# Adafruit_LIS3MDL_LSM6DSOX_FeatherWing.net
KiCad netlist of a schematic drawn in EAGLE
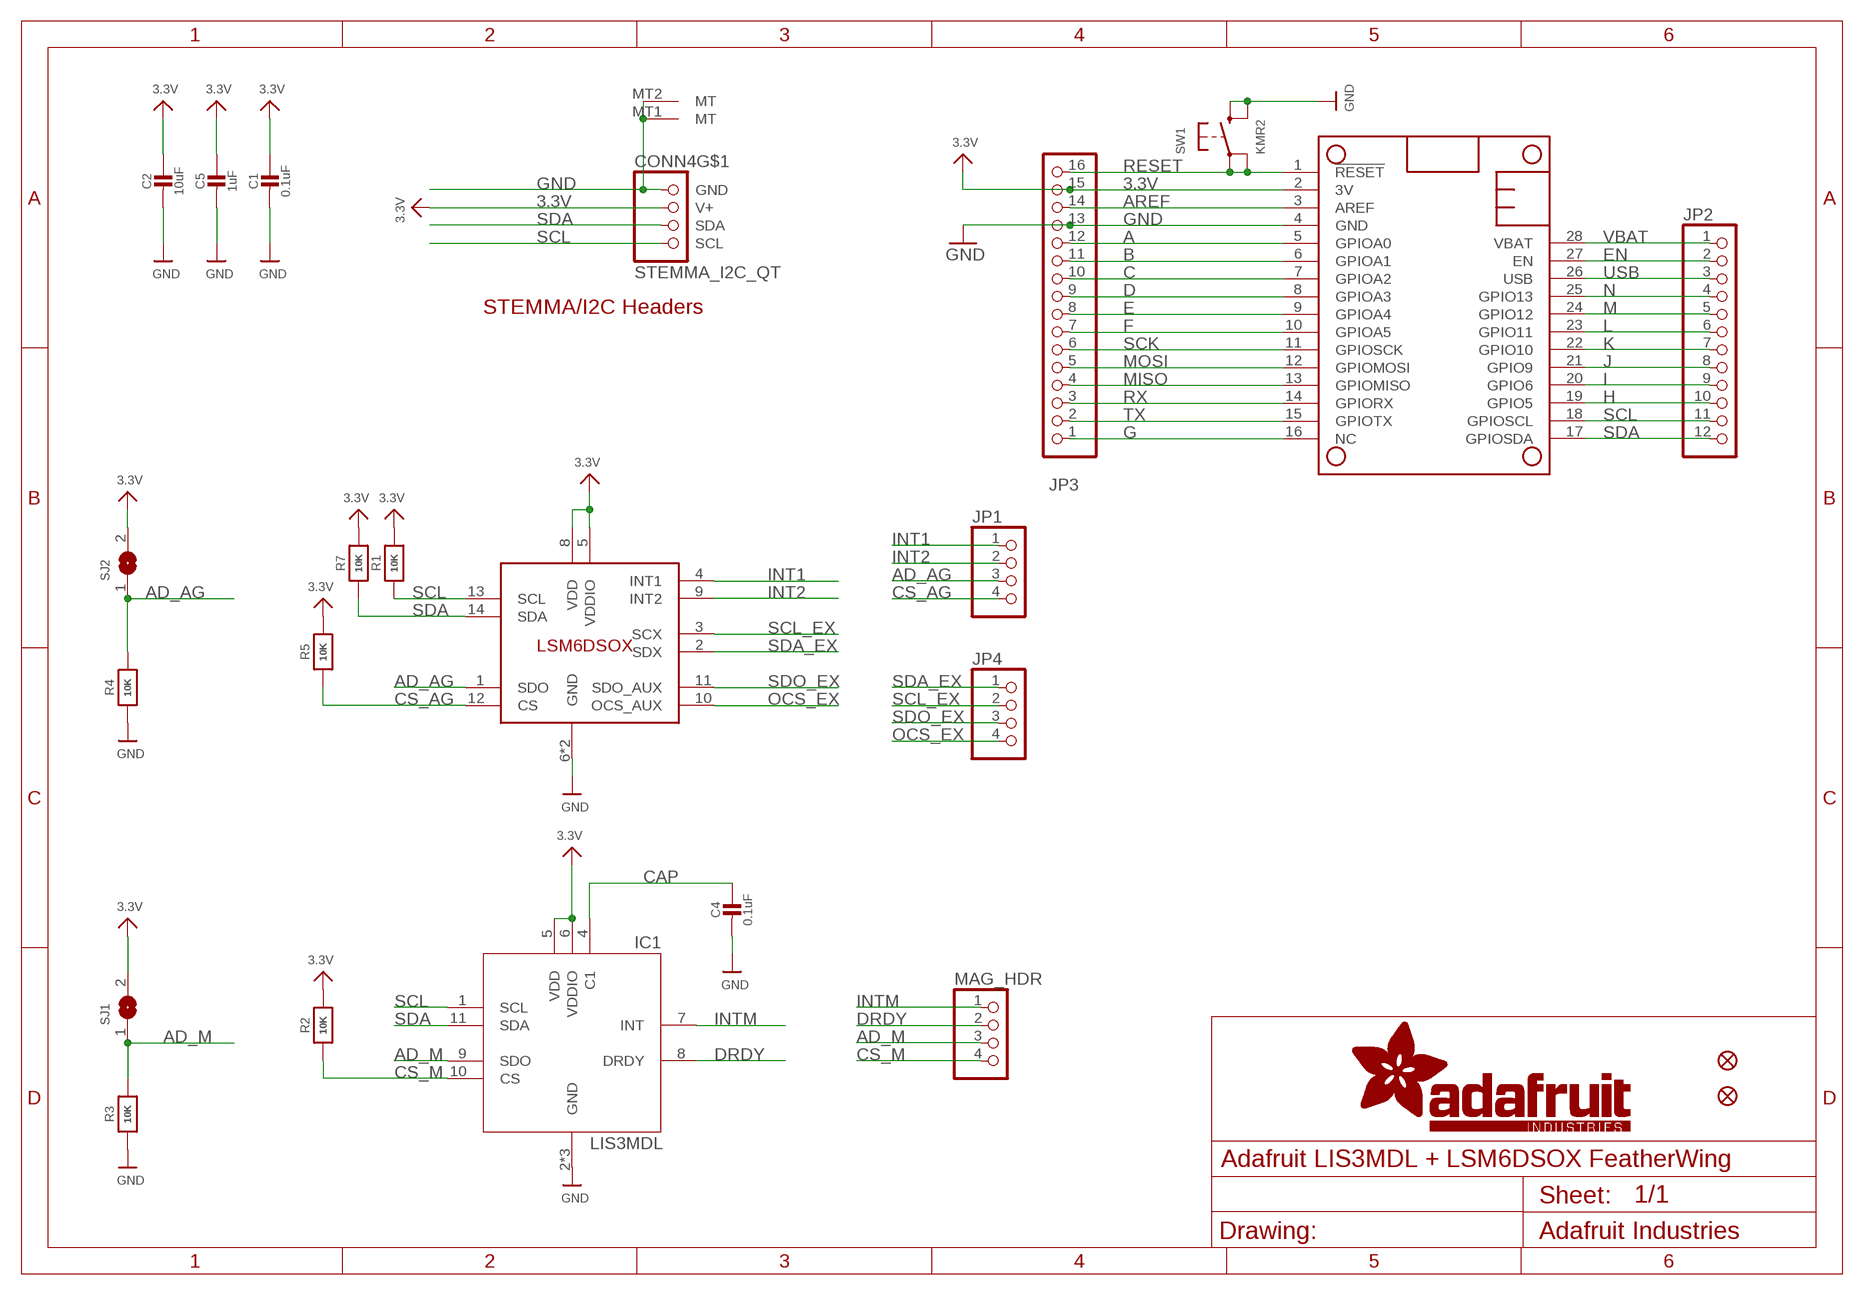
[diagram p0: schematic, sheet 1]

(export (version "E")
  (design (tool "Eeschema 10.0.6"))
  (components
    (comp (ref "C1")
      (value "0.1uF")
      (footprint "eagle-import:0603-NO")
      (libsource (lib "eagle-import") (part "CAP_CERAMIC0603_NO"))
    )
    (comp (ref "C2")
      (value "10uF")
      (footprint "eagle-import:0805-NO")
      (libsource (lib "eagle-import") (part "CAP_CERAMIC0805-NOOUTLINE"))
    )
    (comp (ref "C4")
      (value "0.1uF")
      (footprint "eagle-import:0603-NO")
      (libsource (lib "eagle-import") (part "CAP_CERAMIC0603_NO"))
    )
    (comp (ref "C5")
      (value "1uF")
      (footprint "eagle-import:0603-NO")
      (libsource (lib "eagle-import") (part "CAP_CERAMIC0603_NO"))
    )
    (comp (ref "CONN4")
      (value "STEMMA_I2C_QT")
      (footprint "eagle-import:JST_SH4")
      (libsource (lib "eagle-import") (part "STEMMA_I2C_QT"))
    )
    (comp (ref "FID1")
      (value "FIDUCIAL_1MM")
      (footprint "eagle-import:FIDUCIAL_1MM")
      (libsource (lib "eagle-import") (part "FIDUCIAL_1MM"))
    )
    (comp (ref "FID2")
      (value "FIDUCIAL_1MM")
      (footprint "eagle-import:FIDUCIAL_1MM")
      (libsource (lib "eagle-import") (part "FIDUCIAL_1MM"))
    )
    (comp (ref "IC1")
      (value "LIS3MDL")
      (footprint "eagle-import:LGA12_2X2MM")
      (libsource (lib "eagle-import") (part "LIS3MDL"))
    )
    (comp (ref "JP1")
      (value "HEADER-1X4ROUND")
      (footprint "eagle-import:1X04_ROUND")
      (libsource (lib "eagle-import") (part "HEADER-1X4ROUND"))
    )
    (comp (ref "JP2")
      (value "HEADER-1X12")
      (footprint "eagle-import:1X12_ROUND")
      (libsource (lib "eagle-import") (part "HEADER-1X12"))
    )
    (comp (ref "JP3")
      (value "HEADER-1X16ROUND")
      (footprint "eagle-import:1X16_ROUND")
      (libsource (lib "eagle-import") (part "HEADER-1X16ROUND"))
    )
    (comp (ref "JP4")
      (value "HEADER-1X4ROUND")
      (footprint "eagle-import:1X04_ROUND")
      (libsource (lib "eagle-import") (part "HEADER-1X4ROUND"))
    )
    (comp (ref "MAG_HDR")
      (value "HEADER-1X4ROUND")
      (footprint "eagle-import:1X04_ROUND")
      (libsource (lib "eagle-import") (part "HEADER-1X4ROUND"))
    )
    (comp (ref "MS1")
      (value "FEATHERWING")
      (footprint "eagle-import:FEATHERWING")
      (libsource (lib "eagle-import") (part "FEATHERWING"))
    )
    (comp (ref "R1")
      (value "10K")
      (footprint "eagle-import:0603-NO")
      (libsource (lib "eagle-import") (part "RESISTOR_0603_NOOUT"))
    )
    (comp (ref "R2")
      (value "10K")
      (footprint "eagle-import:0603-NO")
      (libsource (lib "eagle-import") (part "RESISTOR_0603_NOOUT"))
    )
    (comp (ref "R3")
      (value "10K")
      (footprint "eagle-import:0603-NO")
      (libsource (lib "eagle-import") (part "RESISTOR_0603_NOOUT"))
    )
    (comp (ref "R4")
      (value "10K")
      (footprint "eagle-import:0603-NO")
      (libsource (lib "eagle-import") (part "RESISTOR_0603_NOOUT"))
    )
    (comp (ref "R5")
      (value "10K")
      (footprint "eagle-import:0603-NO")
      (libsource (lib "eagle-import") (part "RESISTOR_0603_NOOUT"))
    )
    (comp (ref "R7")
      (value "10K")
      (footprint "eagle-import:0603-NO")
      (libsource (lib "eagle-import") (part "RESISTOR_0603_NOOUT"))
    )
    (comp (ref "SJ1")
      (value "SOLDERJUMPER")
      (footprint "eagle-import:SOLDERJUMPER_ARROW_NOPASTE")
      (libsource (lib "eagle-import") (part "SOLDERJUMPER"))
    )
    (comp (ref "SJ2")
      (value "SOLDERJUMPER")
      (footprint "eagle-import:SOLDERJUMPER_ARROW_NOPASTE")
      (libsource (lib "eagle-import") (part "SOLDERJUMPER"))
    )
    (comp (ref "SW1")
      (value "KMR2")
      (footprint "eagle-import:BTN_KMR2_4.6X2.8")
      (libsource (lib "eagle-import") (part "SWITCH_TACT_SMT4.6X2.8"))
    )
    (comp (ref "U$35")
      (value "LSM6DSOX")
      (footprint "eagle-import:LGA-14L")
      (libsource (lib "eagle-import") (part "LSM6DSOX"))
    )
  )
  (nets
    (net (code "1") (name "/A") (class "Default")
      (node (ref "JP3") (pin "12") (pinfunction "12_12") (pintype "passive"))
      (node (ref "MS1") (pin "5") (pinfunction "GPIOA0_5") (pintype "bidirectional"))
    )
    (net (code "2") (name "/AD_AG") (class "Default")
      (node (ref "JP1") (pin "3") (pinfunction "3_3") (pintype "passive"))
      (node (ref "R4") (pin "2") (pinfunction "2_2") (pintype "passive"))
      (node (ref "SJ2") (pin "1") (pinfunction "1_1") (pintype "passive"))
      (node (ref "U$35") (pin "1") (pinfunction "SDO_1") (pintype "bidirectional"))
    )
    (net (code "3") (name "/AD_M") (class "Default")
      (node (ref "IC1") (pin "9") (pinfunction "SDO_9") (pintype "bidirectional"))
      (node (ref "MAG_HDR") (pin "3") (pinfunction "3_3") (pintype "passive"))
      (node (ref "R3") (pin "2") (pinfunction "2_2") (pintype "passive"))
      (node (ref "SJ1") (pin "1") (pinfunction "1_1") (pintype "passive"))
    )
    (net (code "4") (name "/AREF") (class "Default")
      (node (ref "JP3") (pin "14") (pinfunction "14_14") (pintype "passive"))
      (node (ref "MS1") (pin "3") (pinfunction "AREF_3") (pintype "passive"))
    )
    (net (code "5") (name "/B") (class "Default")
      (node (ref "JP3") (pin "11") (pinfunction "11_11") (pintype "passive"))
      (node (ref "MS1") (pin "6") (pinfunction "GPIOA1_6") (pintype "bidirectional"))
    )
    (net (code "6") (name "/C") (class "Default")
      (node (ref "JP3") (pin "10") (pinfunction "10_10") (pintype "passive"))
      (node (ref "MS1") (pin "7") (pinfunction "GPIOA2_7") (pintype "bidirectional"))
    )
    (net (code "7") (name "/CAP") (class "Default")
      (node (ref "C4") (pin "1") (pinfunction "1_1") (pintype "passive"))
      (node (ref "IC1") (pin "4") (pinfunction "C1_4") (pintype "input"))
    )
    (net (code "8") (name "/CS_AG") (class "Default")
      (node (ref "JP1") (pin "4") (pinfunction "4_4") (pintype "passive"))
      (node (ref "R5") (pin "1") (pinfunction "1_1") (pintype "passive"))
      (node (ref "U$35") (pin "12") (pinfunction "CS_12") (pintype "bidirectional"))
    )
    (net (code "9") (name "/CS_M") (class "Default")
      (node (ref "IC1") (pin "10") (pinfunction "CS_10") (pintype "input"))
      (node (ref "MAG_HDR") (pin "4") (pinfunction "4_4") (pintype "passive"))
      (node (ref "R2") (pin "1") (pinfunction "1_1") (pintype "passive"))
    )
    (net (code "10") (name "/D") (class "Default")
      (node (ref "JP3") (pin "9") (pinfunction "9_9") (pintype "passive"))
      (node (ref "MS1") (pin "8") (pinfunction "GPIOA3_8") (pintype "bidirectional"))
    )
    (net (code "11") (name "/DRDY") (class "Default")
      (node (ref "IC1") (pin "8") (pinfunction "DRDY_8") (pintype "output"))
      (node (ref "MAG_HDR") (pin "2") (pinfunction "2_2") (pintype "passive"))
    )
    (net (code "12") (name "/E") (class "Default")
      (node (ref "JP3") (pin "8") (pinfunction "8_8") (pintype "passive"))
      (node (ref "MS1") (pin "9") (pinfunction "GPIOA4_9") (pintype "bidirectional"))
    )
    (net (code "13") (name "/EN") (class "Default")
      (node (ref "JP2") (pin "2") (pinfunction "2_2") (pintype "passive"))
      (node (ref "MS1") (pin "27") (pinfunction "EN_27") (pintype "passive"))
    )
    (net (code "14") (name "/F") (class "Default")
      (node (ref "JP3") (pin "7") (pinfunction "7_7") (pintype "passive"))
      (node (ref "MS1") (pin "10") (pinfunction "GPIOA5_10") (pintype "bidirectional"))
    )
    (net (code "15") (name "/G") (class "Default")
      (node (ref "JP3") (pin "1") (pinfunction "1_1") (pintype "passive"))
      (node (ref "MS1") (pin "16") (pinfunction "NC_16") (pintype "passive"))
    )
    (net (code "16") (name "/H") (class "Default")
      (node (ref "JP2") (pin "10") (pinfunction "10_10") (pintype "passive"))
      (node (ref "MS1") (pin "19") (pinfunction "GPIO5_19") (pintype "bidirectional"))
    )
    (net (code "17") (name "/I") (class "Default")
      (node (ref "JP2") (pin "9") (pinfunction "9_9") (pintype "passive"))
      (node (ref "MS1") (pin "20") (pinfunction "GPIO6_20") (pintype "bidirectional"))
    )
    (net (code "18") (name "/INT1") (class "Default")
      (node (ref "JP1") (pin "1") (pinfunction "1_1") (pintype "passive"))
      (node (ref "U$35") (pin "4") (pinfunction "INT1_4") (pintype "bidirectional"))
    )
    (net (code "19") (name "/INT2") (class "Default")
      (node (ref "JP1") (pin "2") (pinfunction "2_2") (pintype "passive"))
      (node (ref "U$35") (pin "9") (pinfunction "INT2_9") (pintype "bidirectional"))
    )
    (net (code "20") (name "/INTM") (class "Default")
      (node (ref "IC1") (pin "7") (pinfunction "INT_7") (pintype "output"))
      (node (ref "MAG_HDR") (pin "1") (pinfunction "1_1") (pintype "passive"))
    )
    (net (code "21") (name "/J") (class "Default")
      (node (ref "JP2") (pin "8") (pinfunction "8_8") (pintype "passive"))
      (node (ref "MS1") (pin "21") (pinfunction "GPIO9_21") (pintype "bidirectional"))
    )
    (net (code "22") (name "/K") (class "Default")
      (node (ref "JP2") (pin "7") (pinfunction "7_7") (pintype "passive"))
      (node (ref "MS1") (pin "22") (pinfunction "GPIO10_22") (pintype "bidirectional"))
    )
    (net (code "23") (name "/L") (class "Default")
      (node (ref "JP2") (pin "6") (pinfunction "6_6") (pintype "passive"))
      (node (ref "MS1") (pin "23") (pinfunction "GPIO11_23") (pintype "bidirectional"))
    )
    (net (code "24") (name "/M") (class "Default")
      (node (ref "JP2") (pin "5") (pinfunction "5_5") (pintype "passive"))
      (node (ref "MS1") (pin "24") (pinfunction "GPIO12_24") (pintype "bidirectional"))
    )
    (net (code "25") (name "/MISO") (class "Default")
      (node (ref "JP3") (pin "4") (pinfunction "4_4") (pintype "passive"))
      (node (ref "MS1") (pin "13") (pinfunction "GPIOMISO_13") (pintype "bidirectional"))
    )
    (net (code "26") (name "/MOSI") (class "Default")
      (node (ref "JP3") (pin "5") (pinfunction "5_5") (pintype "passive"))
      (node (ref "MS1") (pin "12") (pinfunction "GPIOMOSI_12") (pintype "bidirectional"))
    )
    (net (code "27") (name "/N") (class "Default")
      (node (ref "JP2") (pin "4") (pinfunction "4_4") (pintype "passive"))
      (node (ref "MS1") (pin "25") (pinfunction "GPIO13_25") (pintype "bidirectional"))
    )
    (net (code "28") (name "/OCS_EX") (class "Default")
      (node (ref "JP4") (pin "4") (pinfunction "4_4") (pintype "passive"))
      (node (ref "U$35") (pin "10") (pinfunction "OCS_AUX_10") (pintype "bidirectional"))
    )
    (net (code "29") (name "/RESET") (class "Default")
      (node (ref "JP3") (pin "16") (pinfunction "16_16") (pintype "passive"))
      (node (ref "MS1") (pin "1") (pinfunction "~{RESET}_1") (pintype "input"))
      (node (ref "SW1") (pin "A") (pinfunction "P_A") (pintype "passive"))
      (node (ref "SW1") (pin "A'") (pinfunction "P1_A'") (pintype "passive"))
    )
    (net (code "30") (name "/RX") (class "Default")
      (node (ref "JP3") (pin "3") (pinfunction "3_3") (pintype "passive"))
      (node (ref "MS1") (pin "14") (pinfunction "GPIORX_14") (pintype "bidirectional"))
    )
    (net (code "31") (name "/SCK") (class "Default")
      (node (ref "JP3") (pin "6") (pinfunction "6_6") (pintype "passive"))
      (node (ref "MS1") (pin "11") (pinfunction "GPIOSCK_11") (pintype "bidirectional"))
    )
    (net (code "32") (name "/SCL") (class "Default")
      (node (ref "CONN4") (pin "4") (pinfunction "SCL_4") (pintype "passive"))
      (node (ref "IC1") (pin "1") (pinfunction "SCL_1") (pintype "input"))
      (node (ref "JP2") (pin "11") (pinfunction "11_11") (pintype "passive"))
      (node (ref "MS1") (pin "18") (pinfunction "GPIOSCL_18") (pintype "bidirectional"))
      (node (ref "R1") (pin "1") (pinfunction "1_1") (pintype "passive"))
      (node (ref "U$35") (pin "13") (pinfunction "SCL_13") (pintype "bidirectional"))
    )
    (net (code "33") (name "/SCL_EX") (class "Default")
      (node (ref "JP4") (pin "2") (pinfunction "2_2") (pintype "passive"))
      (node (ref "U$35") (pin "3") (pinfunction "SCX_3") (pintype "bidirectional"))
    )
    (net (code "34") (name "/SDA") (class "Default")
      (node (ref "CONN4") (pin "3") (pinfunction "SDA_3") (pintype "passive"))
      (node (ref "IC1") (pin "11") (pinfunction "SDA_11") (pintype "bidirectional"))
      (node (ref "JP2") (pin "12") (pinfunction "12_12") (pintype "passive"))
      (node (ref "MS1") (pin "17") (pinfunction "GPIOSDA_17") (pintype "bidirectional"))
      (node (ref "R7") (pin "1") (pinfunction "1_1") (pintype "passive"))
      (node (ref "U$35") (pin "14") (pinfunction "SDA_14") (pintype "bidirectional"))
    )
    (net (code "35") (name "/SDA_EX") (class "Default")
      (node (ref "JP4") (pin "1") (pinfunction "1_1") (pintype "passive"))
      (node (ref "U$35") (pin "2") (pinfunction "SDX_2") (pintype "bidirectional"))
    )
    (net (code "36") (name "/SDO_EX") (class "Default")
      (node (ref "JP4") (pin "3") (pinfunction "3_3") (pintype "passive"))
      (node (ref "U$35") (pin "11") (pinfunction "SDO_AUX_11") (pintype "bidirectional"))
    )
    (net (code "37") (name "/TX") (class "Default")
      (node (ref "JP3") (pin "2") (pinfunction "2_2") (pintype "passive"))
      (node (ref "MS1") (pin "15") (pinfunction "GPIOTX_15") (pintype "bidirectional"))
    )
    (net (code "38") (name "/USB") (class "Default")
      (node (ref "JP2") (pin "3") (pinfunction "3_3") (pintype "passive"))
      (node (ref "MS1") (pin "26") (pinfunction "USB_26") (pintype "power_in"))
    )
    (net (code "39") (name "/VBAT") (class "Default")
      (node (ref "JP2") (pin "1") (pinfunction "1_1") (pintype "passive"))
      (node (ref "MS1") (pin "28") (pinfunction "VBAT_28") (pintype "power_in"))
    )
    (net (code "40") (name "3.3V") (class "Default")
      (node (ref "C1") (pin "1") (pinfunction "1_1") (pintype "passive"))
      (node (ref "C2") (pin "1") (pinfunction "1_1") (pintype "passive"))
      (node (ref "C5") (pin "1") (pinfunction "1_1") (pintype "passive"))
      (node (ref "CONN4") (pin "2") (pinfunction "V+_2") (pintype "passive"))
      (node (ref "IC1") (pin "5") (pinfunction "VDD_5") (pintype "power_in"))
      (node (ref "IC1") (pin "6") (pinfunction "VDDIO_6") (pintype "power_in"))
      (node (ref "JP3") (pin "15") (pinfunction "15_15") (pintype "passive"))
      (node (ref "MS1") (pin "2") (pinfunction "3V_2") (pintype "power_in"))
      (node (ref "R1") (pin "2") (pinfunction "2_2") (pintype "passive"))
      (node (ref "R2") (pin "2") (pinfunction "2_2") (pintype "passive"))
      (node (ref "R5") (pin "2") (pinfunction "2_2") (pintype "passive"))
      (node (ref "R7") (pin "2") (pinfunction "2_2") (pintype "passive"))
      (node (ref "SJ1") (pin "2") (pinfunction "2_2") (pintype "passive"))
      (node (ref "SJ2") (pin "2") (pinfunction "2_2") (pintype "passive"))
      (node (ref "U$35") (pin "5") (pinfunction "VDDIO_5") (pintype "power_in"))
      (node (ref "U$35") (pin "8") (pinfunction "VDD_8") (pintype "power_in"))
    )
    (net (code "41") (name "GND") (class "Default")
      (node (ref "C1") (pin "2") (pinfunction "2_2") (pintype "passive"))
      (node (ref "C2") (pin "2") (pinfunction "2_2") (pintype "passive"))
      (node (ref "C4") (pin "2") (pinfunction "2_2") (pintype "passive"))
      (node (ref "C5") (pin "2") (pinfunction "2_2") (pintype "passive"))
      (node (ref "CONN4") (pin "1") (pinfunction "GND_1") (pintype "passive"))
      (node (ref "CONN4") (pin "MT1") (pinfunction "MT_MT1") (pintype "bidirectional"))
      (node (ref "CONN4") (pin "MT2") (pinfunction "MT_MT2") (pintype "bidirectional"))
      (node (ref "IC1") (pin "12") (pinfunction "GND_12") (pintype "power_in"))
      (node (ref "IC1") (pin "2") (pinfunction "GND_2") (pintype "power_in"))
      (node (ref "IC1") (pin "3") (pinfunction "GND_3") (pintype "power_in"))
      (node (ref "JP3") (pin "13") (pinfunction "13_13") (pintype "passive"))
      (node (ref "MS1") (pin "4") (pinfunction "GND_4") (pintype "power_in"))
      (node (ref "R3") (pin "1") (pinfunction "1_1") (pintype "passive"))
      (node (ref "R4") (pin "1") (pinfunction "1_1") (pintype "passive"))
      (node (ref "SW1") (pin "B") (pinfunction "S_B") (pintype "passive"))
      (node (ref "SW1") (pin "B'") (pinfunction "S1_B'") (pintype "passive"))
      (node (ref "U$35") (pin "6") (pinfunction "GND_6") (pintype "power_in"))
      (node (ref "U$35") (pin "7") (pinfunction "GND_7") (pintype "power_in"))
    )
  )
)
